# doubleTiny.net
KiCad netlist of a schematic drawn in EAGLE
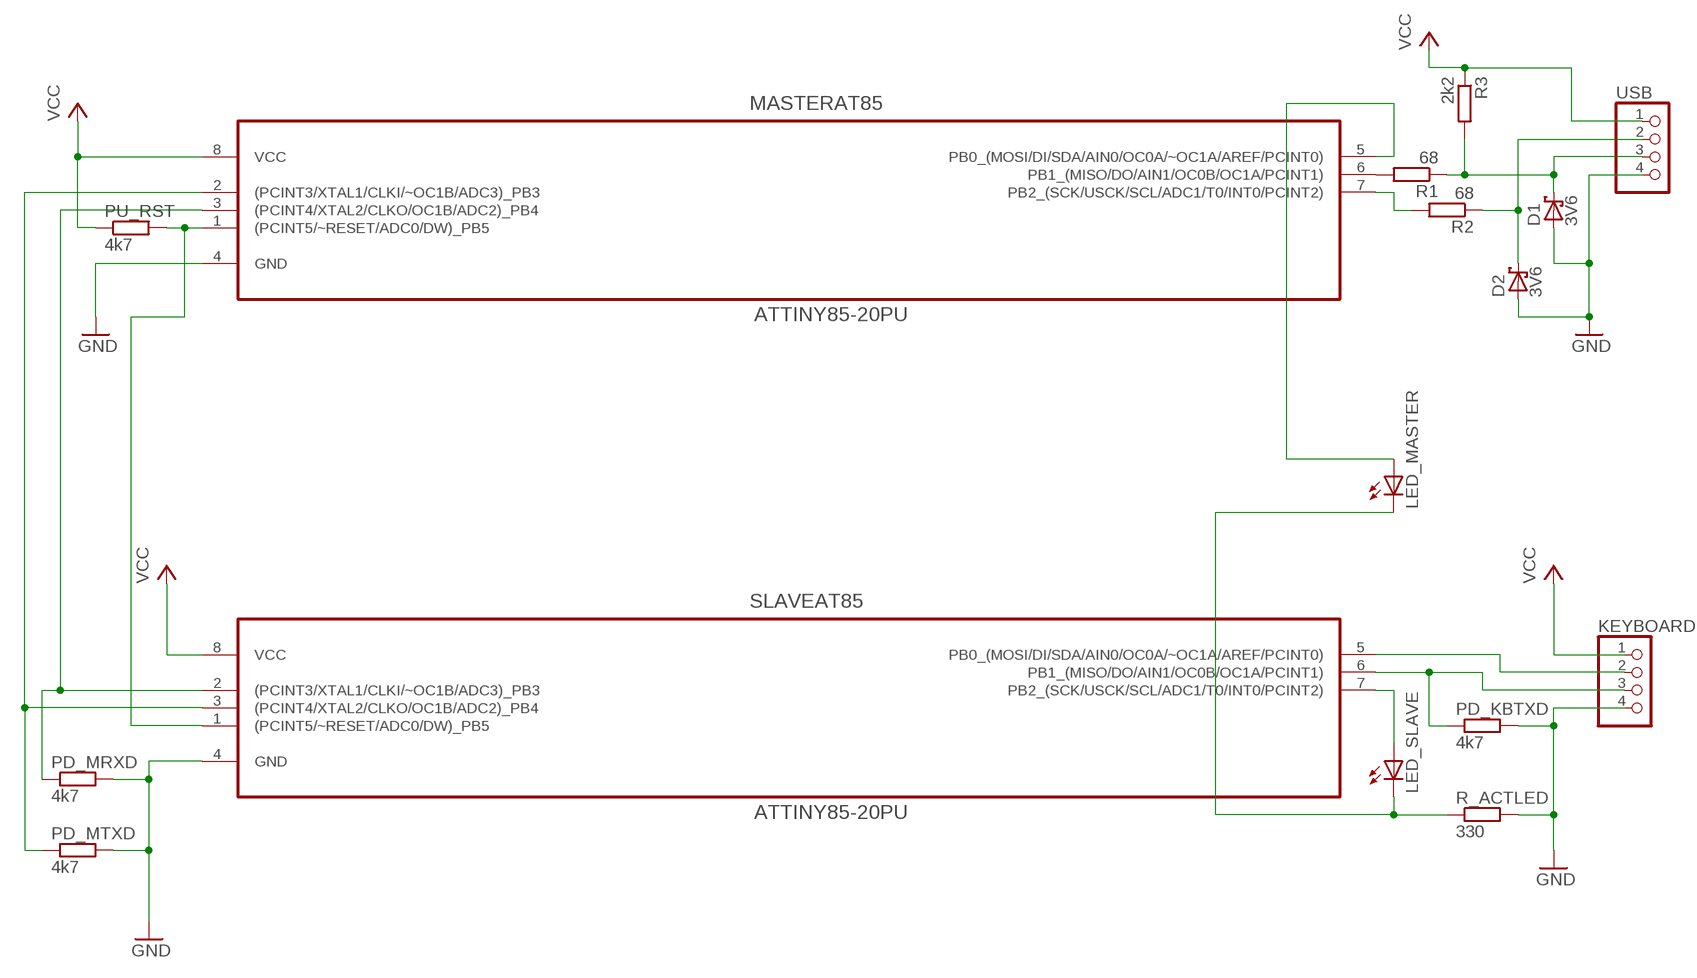
[diagram p0: schematic, sheet 1]

(export (version "E")
  (design (tool "Eeschema 10.0.6"))
  (components
    (comp (ref "D1")
      (value "3V6")
      (footprint "eagle-import:C4111-15")
      (libsource (lib "eagle-import") (part "1N5908"))
    )
    (comp (ref "D2")
      (value "3V6")
      (footprint "eagle-import:C4111-15")
      (libsource (lib "eagle-import") (part "1N5908"))
    )
    (comp (ref "KEYBOARD")
      (value "PINHD-1X4")
      (footprint "eagle-import:1X04")
      (libsource (lib "eagle-import") (part "PINHD-1X4"))
    )
    (comp (ref "LED_MASTER")
      (value "LED3MM")
      (footprint "eagle-import:LED3MM")
      (libsource (lib "eagle-import") (part "LED3MM"))
    )
    (comp (ref "LED_SLAVE")
      (value "LED5MM")
      (footprint "eagle-import:LED5MM")
      (libsource (lib "eagle-import") (part "LED5MM"))
    )
    (comp (ref "MASTERAT85")
      (value "ATTINY85-20PU")
      (footprint "eagle-import:DIP254P762X533-8")
      (libsource (lib "eagle-import") (part "ATTINY85-20PU"))
    )
    (comp (ref "PD_KBTXD")
      (value "4k7")
      (footprint "eagle-import:0309_12")
      (libsource (lib "eagle-import") (part "R-EU_0309/12"))
    )
    (comp (ref "PD_MRXD")
      (value "4k7")
      (footprint "eagle-import:0309_12")
      (libsource (lib "eagle-import") (part "R-EU_0309/12"))
    )
    (comp (ref "PD_MTXD")
      (value "4k7")
      (footprint "eagle-import:0309_12")
      (libsource (lib "eagle-import") (part "R-EU_0309/12"))
    )
    (comp (ref "PU_RST")
      (value "4k7")
      (footprint "eagle-import:0309_12")
      (libsource (lib "eagle-import") (part "R-EU_0309/12"))
    )
    (comp (ref "R1")
      (value "68")
      (footprint "eagle-import:0309_12")
      (libsource (lib "eagle-import") (part "R-EU_0309/12"))
    )
    (comp (ref "R2")
      (value "68")
      (footprint "eagle-import:0309_12")
      (libsource (lib "eagle-import") (part "R-EU_0309/12"))
    )
    (comp (ref "R3")
      (value "2k2")
      (footprint "eagle-import:0309_12")
      (libsource (lib "eagle-import") (part "R-EU_0309/12"))
    )
    (comp (ref "R_ACTLED")
      (value "330")
      (footprint "eagle-import:0309_12")
      (libsource (lib "eagle-import") (part "R-EU_0309/12"))
    )
    (comp (ref "SLAVEAT85")
      (value "ATTINY85-20PU")
      (footprint "eagle-import:DIP254P762X533-8")
      (libsource (lib "eagle-import") (part "ATTINY85-20PU"))
    )
    (comp (ref "USB")
      (value "PINHD-1X4")
      (footprint "eagle-import:1X04")
      (libsource (lib "eagle-import") (part "PINHD-1X4"))
    )
  )
  (nets
    (net (code "1") (name "GND") (class "Default")
      (node (ref "D1") (pin "A") (pinfunction "A_A") (pintype "passive"))
      (node (ref "D2") (pin "A") (pinfunction "A_A") (pintype "passive"))
      (node (ref "KEYBOARD") (pin "4") (pinfunction "4_4") (pintype "passive"))
      (node (ref "MASTERAT85") (pin "4") (pinfunction "GND_4") (pintype "passive"))
      (node (ref "PD_KBTXD") (pin "2") (pinfunction "2_2") (pintype "passive"))
      (node (ref "PD_MRXD") (pin "2") (pinfunction "2_2") (pintype "passive"))
      (node (ref "PD_MTXD") (pin "2") (pinfunction "2_2") (pintype "passive"))
      (node (ref "R_ACTLED") (pin "2") (pinfunction "2_2") (pintype "passive"))
      (node (ref "SLAVEAT85") (pin "4") (pinfunction "GND_4") (pintype "passive"))
      (node (ref "USB") (pin "4") (pinfunction "4_4") (pintype "passive"))
    )
    (net (code "2") (name "Net-(D1-PadC)") (class "Default")
      (node (ref "D1") (pin "C") (pinfunction "C_C") (pintype "passive"))
      (node (ref "R1") (pin "1") (pinfunction "1_1") (pintype "passive"))
      (node (ref "R3") (pin "2") (pinfunction "2_2") (pintype "passive"))
      (node (ref "USB") (pin "3") (pinfunction "3_3") (pintype "passive"))
    )
    (net (code "3") (name "Net-(D2-PadC)") (class "Default")
      (node (ref "D2") (pin "C") (pinfunction "C_C") (pintype "passive"))
      (node (ref "R2") (pin "1") (pinfunction "1_1") (pintype "passive"))
      (node (ref "USB") (pin "2") (pinfunction "2_2") (pintype "passive"))
    )
    (net (code "4") (name "Net-(LED_MASTER-C)") (class "Default")
      (node (ref "LED_MASTER") (pin "K") (pinfunction "C_K") (pintype "passive"))
      (node (ref "LED_SLAVE") (pin "K") (pinfunction "C_K") (pintype "passive"))
      (node (ref "R_ACTLED") (pin "1") (pinfunction "1_1") (pintype "passive"))
    )
    (net (code "5") (name "Net-(MASTERAT85-(PCINT3{slash}XTAL1{slash}CLKI{slash}~{OC1B{slash}ADC3})_PB3)") (class "Default")
      (node (ref "MASTERAT85") (pin "2") (pinfunction "(PCINT3/XTAL1/CLKI/~{OC1B/ADC3})_PB3_2") (pintype "bidirectional"))
      (node (ref "PD_MTXD") (pin "1") (pinfunction "1_1") (pintype "passive"))
      (node (ref "SLAVEAT85") (pin "3") (pinfunction "(PCINT4/XTAL2/CLKO/OC1B/ADC2)_PB4_3") (pintype "bidirectional"))
    )
    (net (code "6") (name "Net-(MASTERAT85-(PCINT4{slash}XTAL2{slash}CLKO{slash}OC1B{slash}ADC2)_PB4)") (class "Default")
      (node (ref "MASTERAT85") (pin "3") (pinfunction "(PCINT4/XTAL2/CLKO/OC1B/ADC2)_PB4_3") (pintype "bidirectional"))
      (node (ref "PD_MRXD") (pin "1") (pinfunction "1_1") (pintype "passive"))
      (node (ref "SLAVEAT85") (pin "2") (pinfunction "(PCINT3/XTAL1/CLKI/~{OC1B/ADC3})_PB3_2") (pintype "bidirectional"))
    )
    (net (code "7") (name "Net-(MASTERAT85-(PCINT5{slash}~{RESET{slash}ADC0{slash}DW})_PB5)") (class "Default")
      (node (ref "MASTERAT85") (pin "1") (pinfunction "(PCINT5/~{RESET/ADC0/DW})_PB5_1") (pintype "bidirectional"))
      (node (ref "PU_RST") (pin "2") (pinfunction "2_2") (pintype "passive"))
      (node (ref "SLAVEAT85") (pin "1") (pinfunction "(PCINT5/~{RESET/ADC0/DW})_PB5_1") (pintype "bidirectional"))
    )
    (net (code "8") (name "Net-(MASTERAT85-PB0_(MOSI{slash}DI{slash}SDA{slash}AIN0{slash}OC0A{slash}~{OC1A{slash}AREF{slash}PCINT0}))") (class "Default")
      (node (ref "LED_MASTER") (pin "A") (pinfunction "A_A") (pintype "passive"))
      (node (ref "MASTERAT85") (pin "5") (pinfunction "PB0_(MOSI/DI/SDA/AIN0/OC0A/~{OC1A/AREF/PCINT0})_5") (pintype "bidirectional"))
    )
    (net (code "9") (name "Net-(MASTERAT85-PB1_(MISO{slash}DO{slash}AIN1{slash}OC0B{slash}OC1A{slash}PCINT1))") (class "Default")
      (node (ref "MASTERAT85") (pin "6") (pinfunction "PB1_(MISO/DO/AIN1/OC0B/OC1A/PCINT1)_6") (pintype "bidirectional"))
      (node (ref "R1") (pin "2") (pinfunction "2_2") (pintype "passive"))
    )
    (net (code "10") (name "Net-(MASTERAT85-PB2_(SCK{slash}USCK{slash}SCL{slash}ADC1{slash}T0{slash}INT0{slash}PCINT2))") (class "Default")
      (node (ref "MASTERAT85") (pin "7") (pinfunction "PB2_(SCK/USCK/SCL/ADC1/T0/INT0/PCINT2)_7") (pintype "bidirectional"))
      (node (ref "R2") (pin "2") (pinfunction "2_2") (pintype "passive"))
    )
    (net (code "11") (name "Net-(SLAVEAT85-PB0_(MOSI{slash}DI{slash}SDA{slash}AIN0{slash}OC0A{slash}~{OC1A{slash}AREF{slash}PCINT0}))") (class "Default")
      (node (ref "KEYBOARD") (pin "2") (pinfunction "2_2") (pintype "passive"))
      (node (ref "SLAVEAT85") (pin "5") (pinfunction "PB0_(MOSI/DI/SDA/AIN0/OC0A/~{OC1A/AREF/PCINT0})_5") (pintype "bidirectional"))
    )
    (net (code "12") (name "Net-(SLAVEAT85-PB1_(MISO{slash}DO{slash}AIN1{slash}OC0B{slash}OC1A{slash}PCINT1))") (class "Default")
      (node (ref "KEYBOARD") (pin "3") (pinfunction "3_3") (pintype "passive"))
      (node (ref "PD_KBTXD") (pin "1") (pinfunction "1_1") (pintype "passive"))
      (node (ref "SLAVEAT85") (pin "6") (pinfunction "PB1_(MISO/DO/AIN1/OC0B/OC1A/PCINT1)_6") (pintype "bidirectional"))
    )
    (net (code "13") (name "Net-(SLAVEAT85-PB2_(SCK{slash}USCK{slash}SCL{slash}ADC1{slash}T0{slash}INT0{slash}PCINT2))") (class "Default")
      (node (ref "LED_SLAVE") (pin "A") (pinfunction "A_A") (pintype "passive"))
      (node (ref "SLAVEAT85") (pin "7") (pinfunction "PB2_(SCK/USCK/SCL/ADC1/T0/INT0/PCINT2)_7") (pintype "bidirectional"))
    )
    (net (code "14") (name "VCC") (class "Default")
      (node (ref "KEYBOARD") (pin "1") (pinfunction "1_1") (pintype "passive"))
      (node (ref "MASTERAT85") (pin "8") (pinfunction "VCC_8") (pintype "power_in"))
      (node (ref "PU_RST") (pin "1") (pinfunction "1_1") (pintype "passive"))
      (node (ref "R3") (pin "1") (pinfunction "1_1") (pintype "passive"))
      (node (ref "SLAVEAT85") (pin "8") (pinfunction "VCC_8") (pintype "power_in"))
      (node (ref "USB") (pin "1") (pinfunction "1_1") (pintype "passive"))
    )
  )
)
